# Micromouse_Arduino_Nano.net
KiCad netlist of a schematic drawn in EAGLE
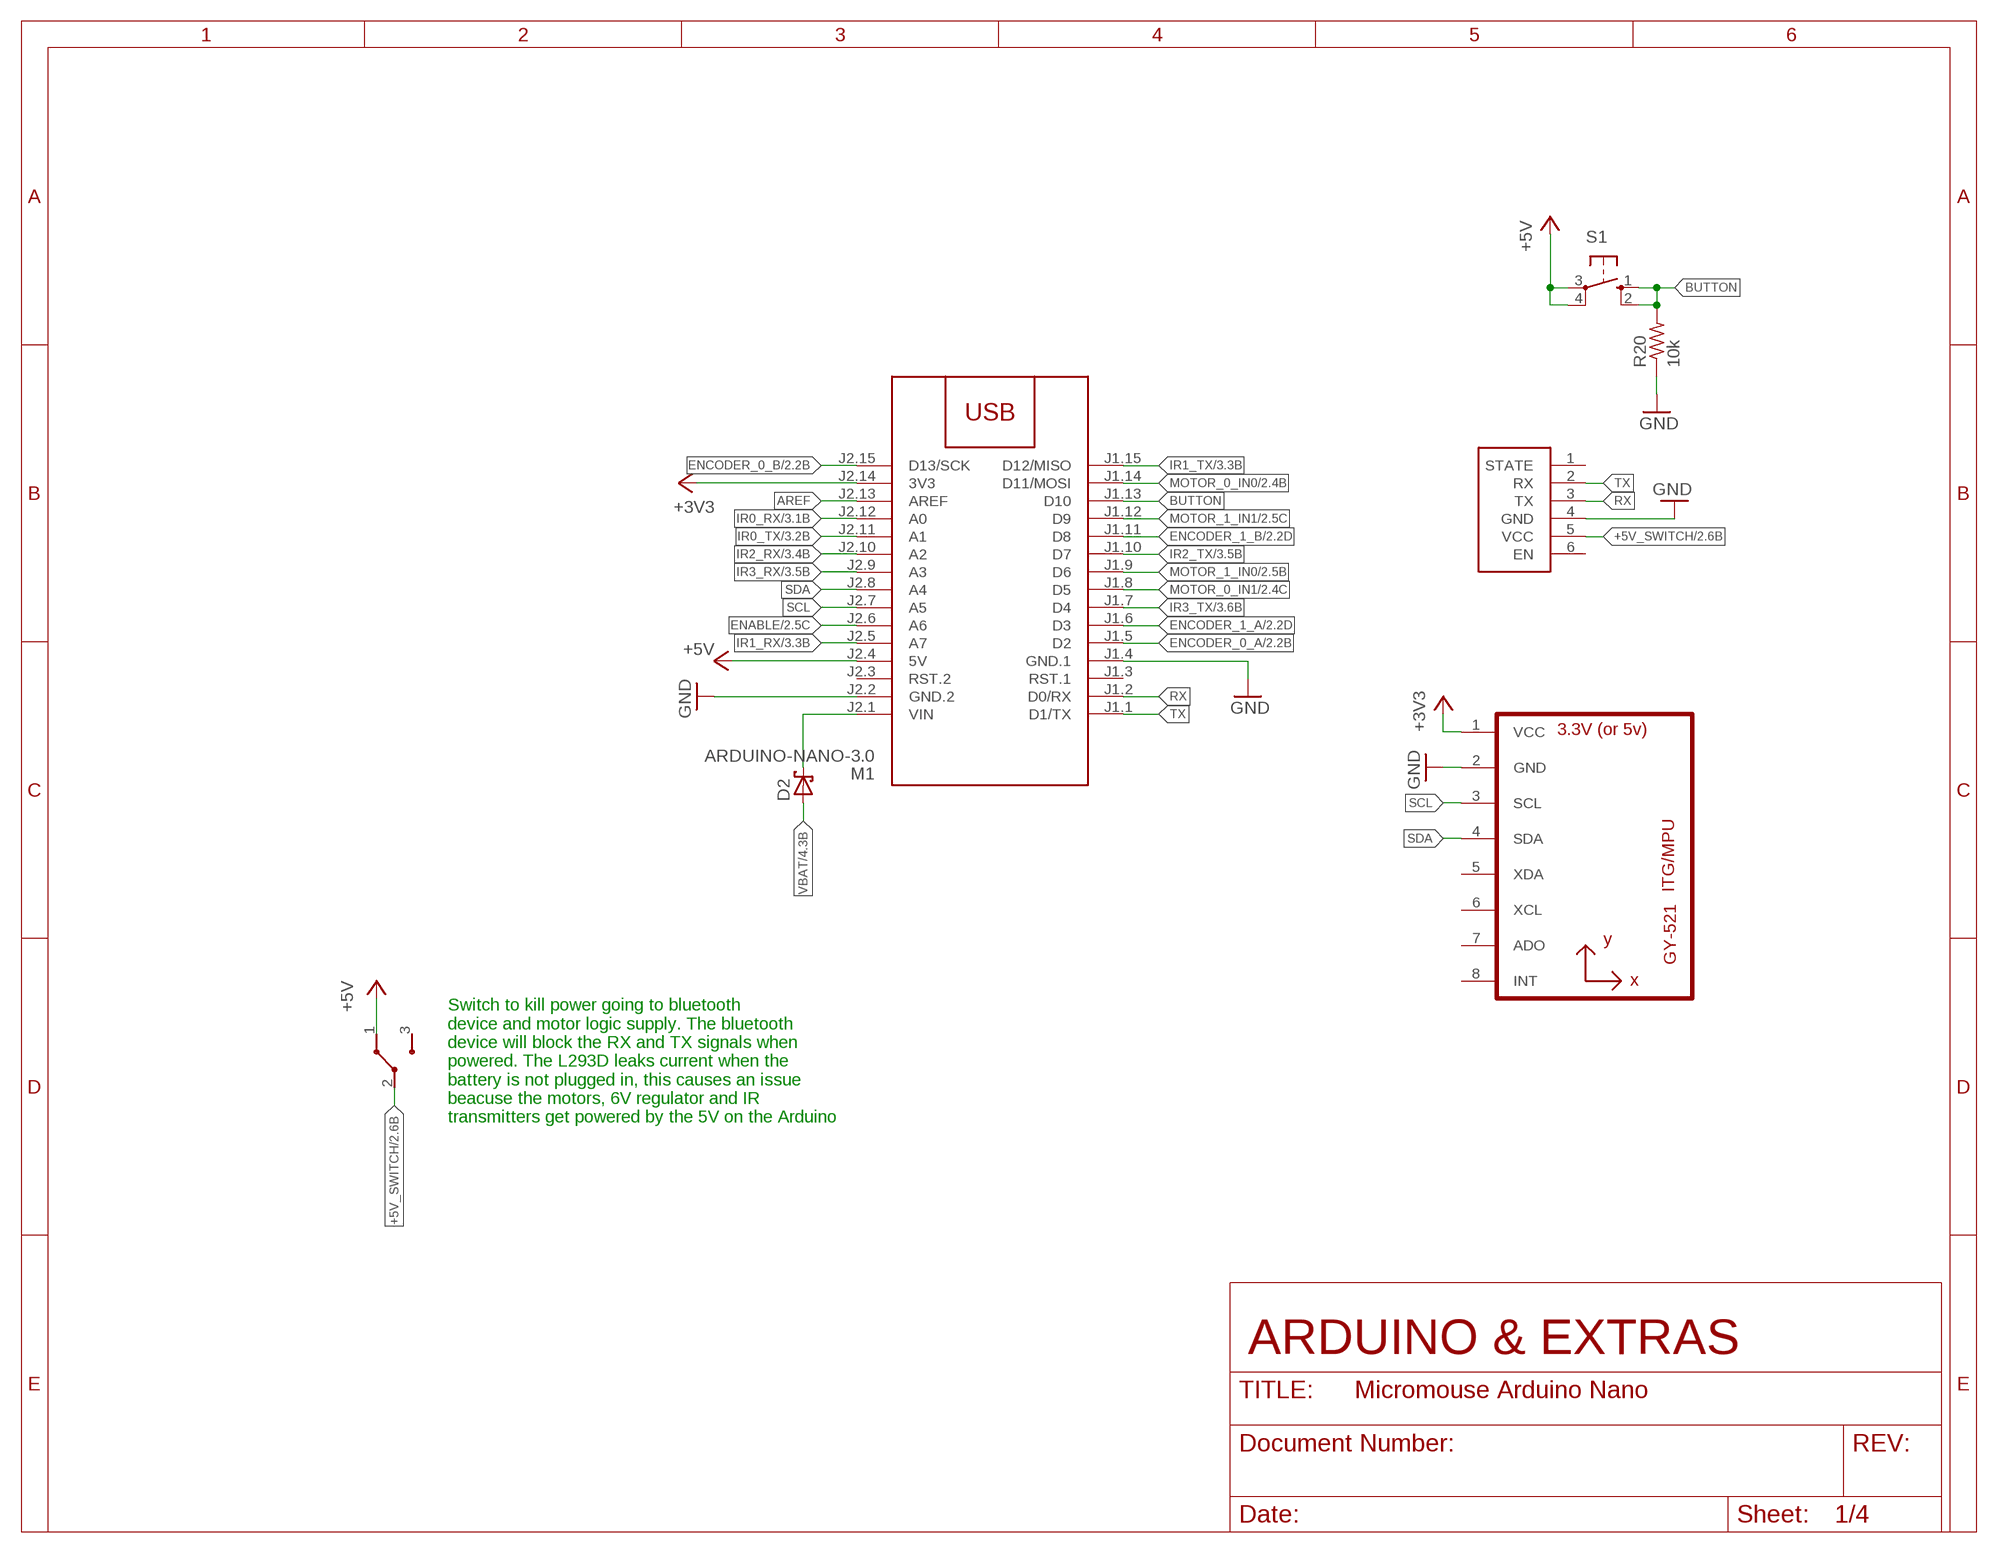
[diagram p0: schematic, sheet 1]
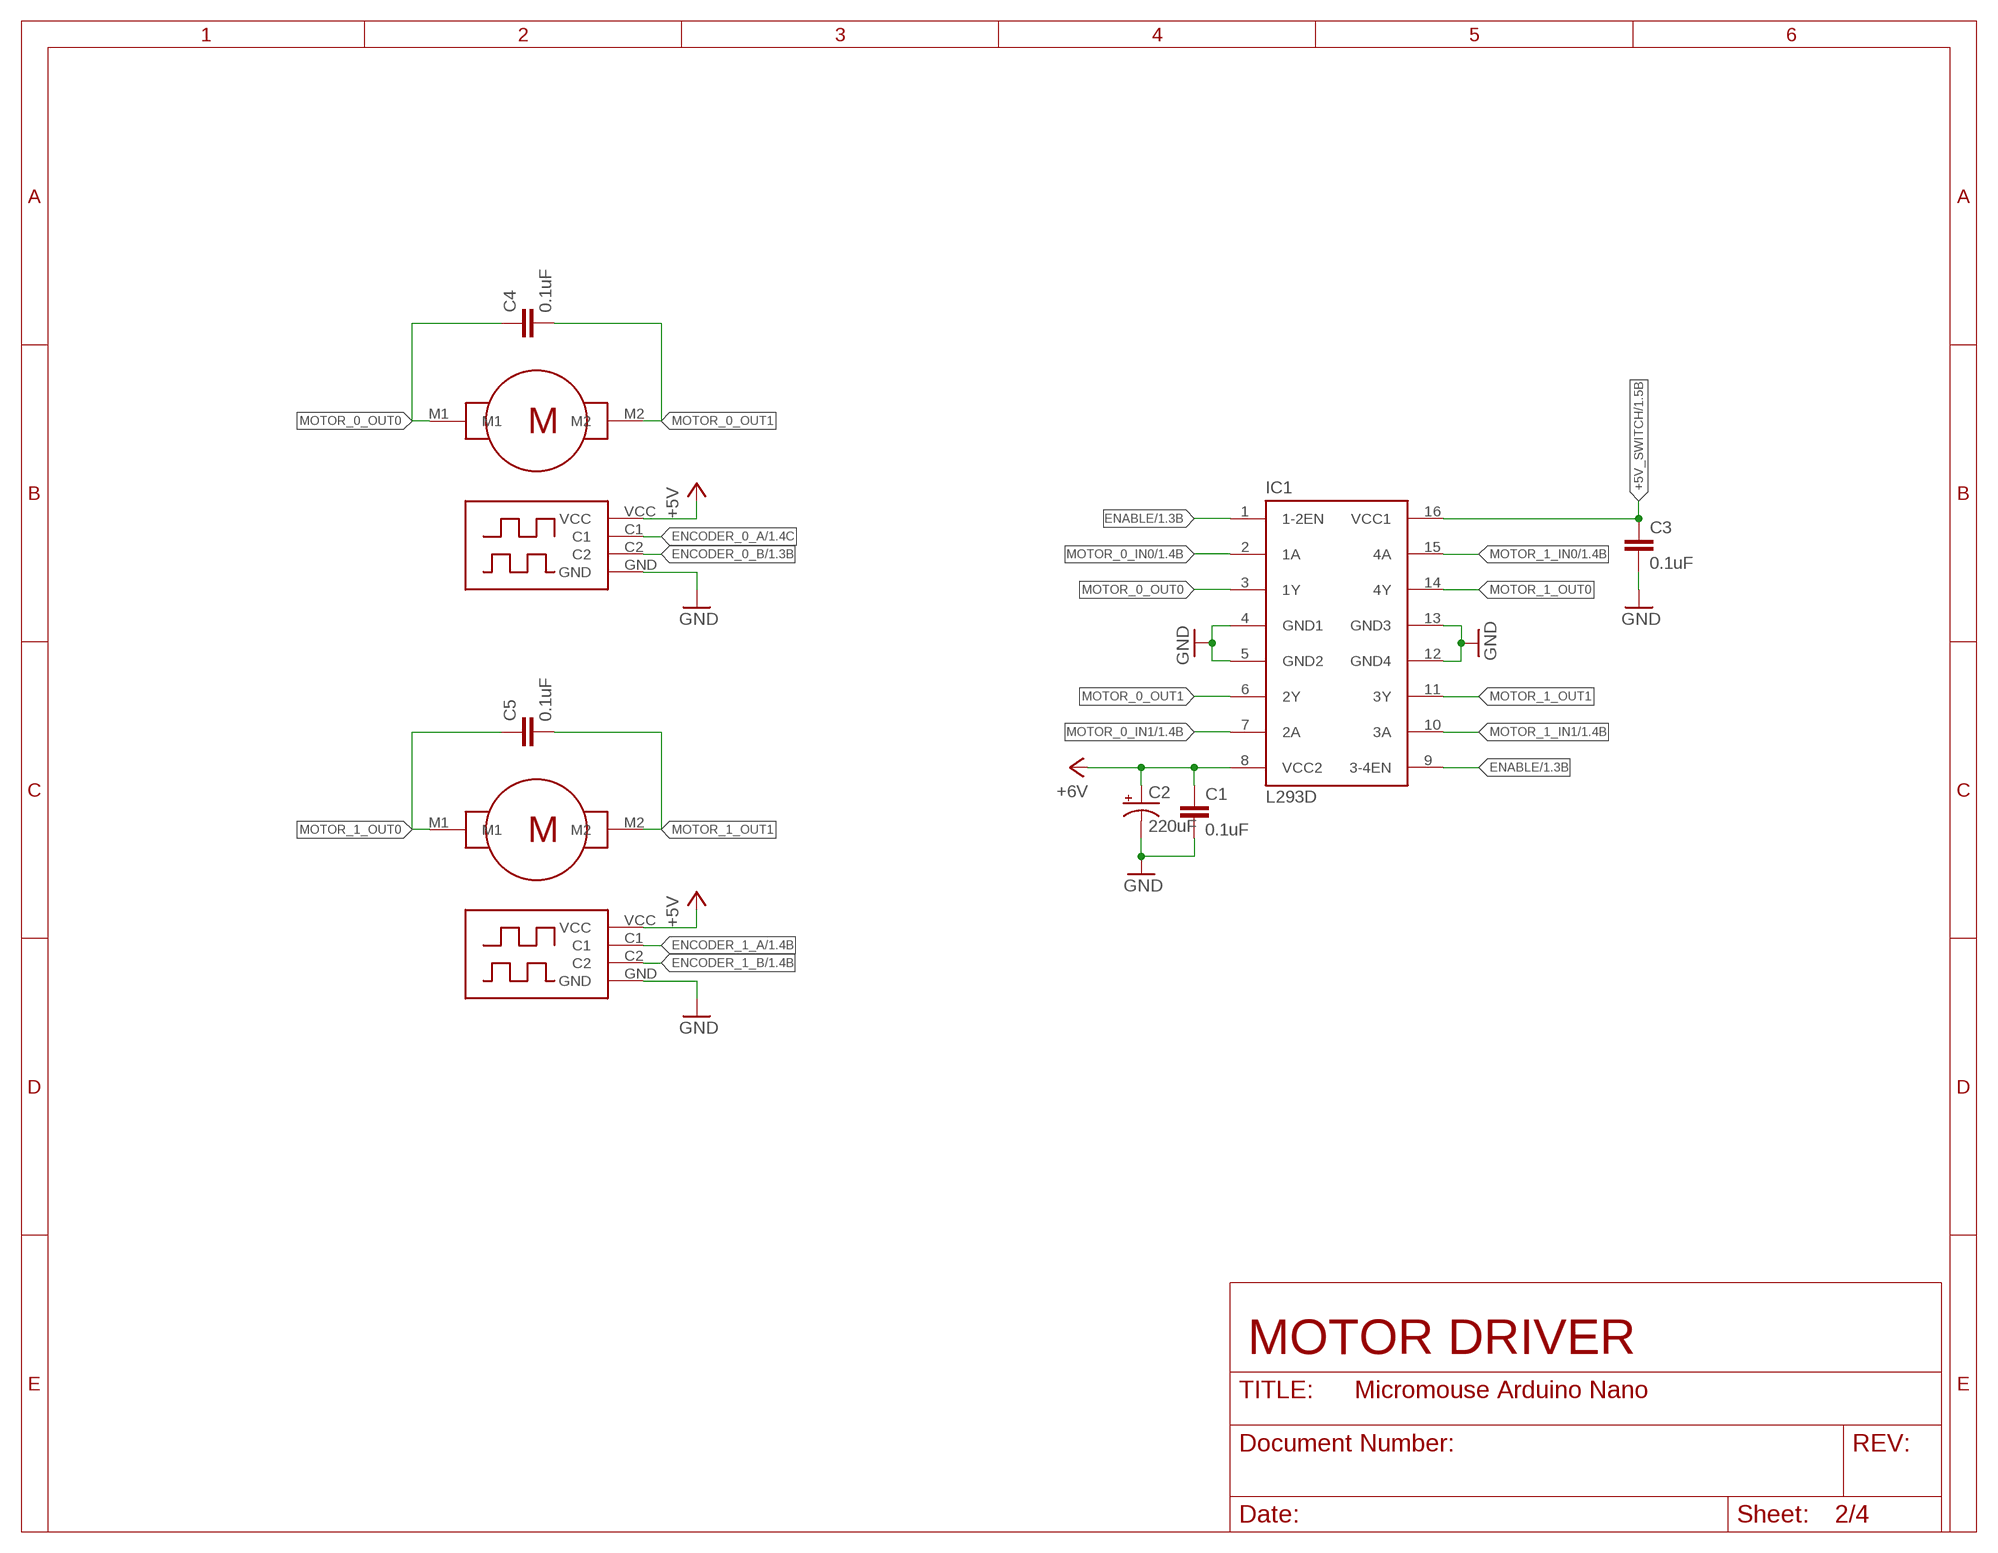
[diagram p1: schematic, sheet 2]
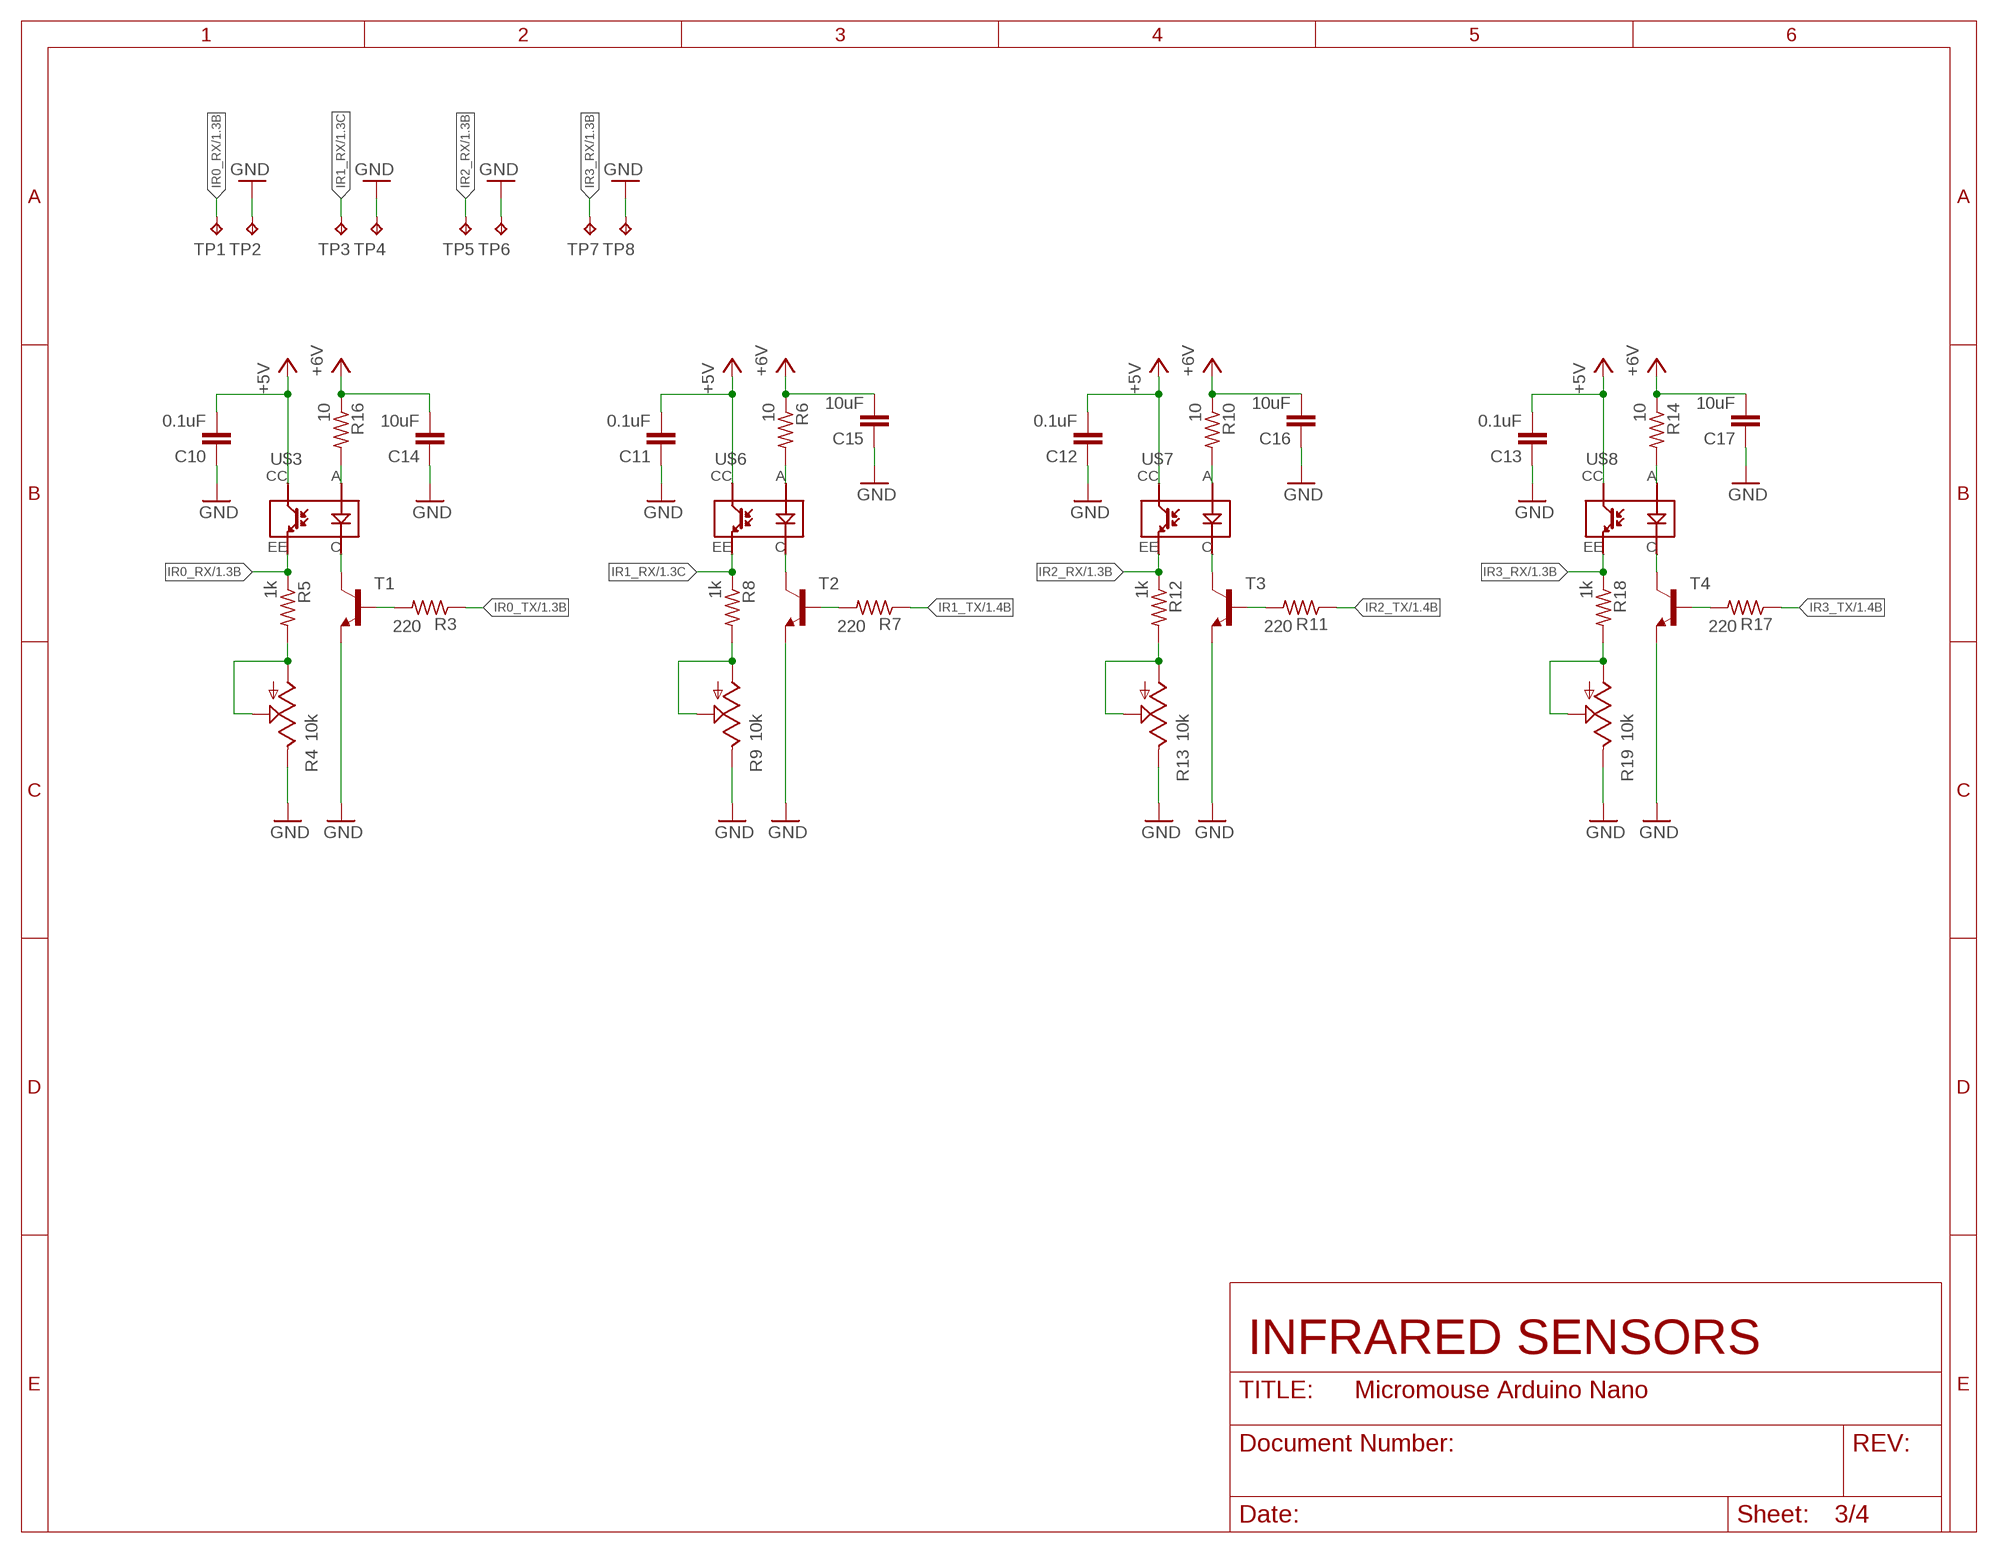
[diagram p2: schematic, sheet 3]
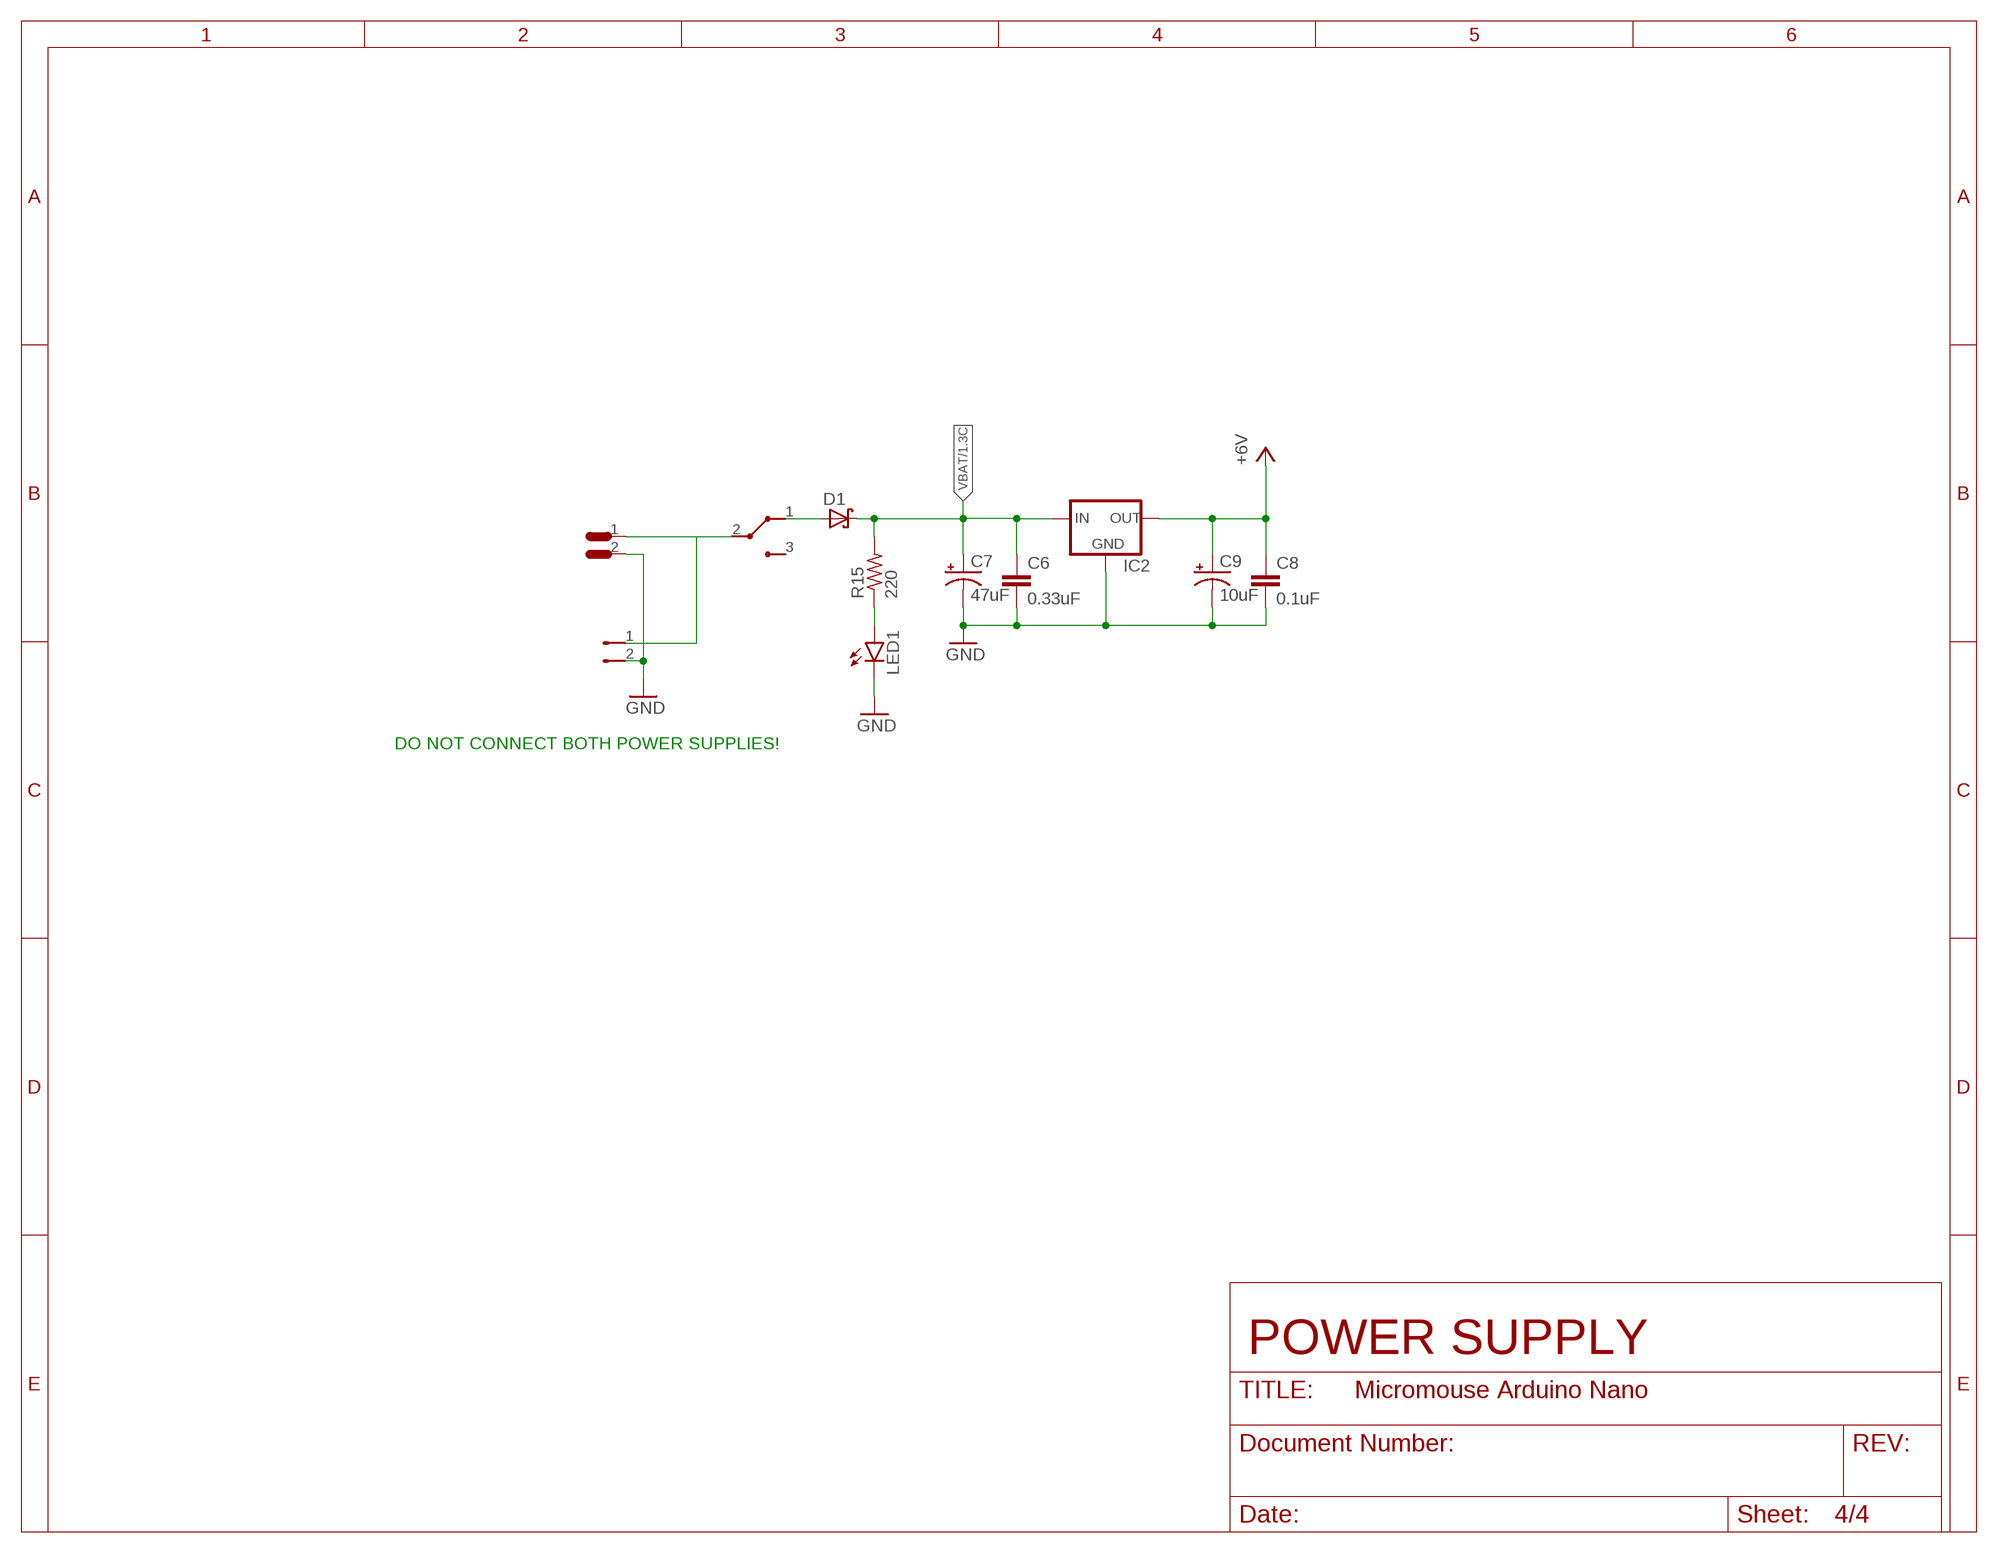
[diagram p3: schematic, sheet 4]

(export (version "E")
  (design (tool "Eeschema 10.0.6"))
  (components
    (comp (ref "C6")
      (value "0.33uF")
      (footprint "eagle-import:C050-025X075")
      (libsource (lib "eagle-import") (part "C-EU050-025X075"))
    )
    (comp (ref "C7")
      (value "47uF")
      (footprint "eagle-import:E2-4")
      (libsource (lib "eagle-import") (part "CPOL-USE2-4"))
    )
    (comp (ref "C8")
      (value "0.1uF")
      (footprint "eagle-import:C050-025X075")
      (libsource (lib "eagle-import") (part "C-EU050-025X075"))
    )
    (comp (ref "C9")
      (value "10uF")
      (footprint "eagle-import:E2,5-5")
      (libsource (lib "eagle-import") (part "CPOL-USE2.5-5"))
    )
    (comp (ref "D1")
      (value "SCHOTTKY-DIODEDO41-7")
      (footprint "eagle-import:DO41-7")
      (libsource (lib "eagle-import") (part "SCHOTTKY-DIODEDO41-7"))
    )
    (comp (ref "IC2")
      (value "78XXS")
      (footprint "eagle-import:78XXS")
      (libsource (lib "eagle-import") (part "78XXS"))
    )
    (comp (ref "LED1")
      (value "LED5MM")
      (footprint "eagle-import:LED5MM")
      (libsource (lib "eagle-import") (part "LED5MM"))
    )
    (comp (ref "R15")
      (value "220")
      (footprint "eagle-import:0207_2V")
      (libsource (lib "eagle-import") (part "R-US_0207/2V"))
    )
    (comp (ref "U$4")
      (value "K3-1260D")
      (footprint "eagle-import:K3-1260D")
      (libsource (lib "eagle-import") (part "K3-1260D"))
    )
    (comp (ref "U$5")
      (value "XT30-M")
      (footprint "eagle-import:XT30-M")
      (libsource (lib "eagle-import") (part "XT30-M"))
    )
    (comp (ref "U$12")
      (value "JST_POWER")
      (footprint "eagle-import:JST_POWER")
      (libsource (lib "eagle-import") (part "JST_POWER"))
    )
    (comp (ref "C1")
      (value "0.1uF")
      (footprint "eagle-import:C050-025X075")
      (libsource (lib "eagle-import") (part "C-EU050-025X075"))
    )
    (comp (ref "C2")
      (value "220uF")
      (footprint "eagle-import:E2,5-6")
      (libsource (lib "eagle-import") (part "CPOL-USE2.5-6"))
    )
    (comp (ref "C3")
      (value "0.1uF")
      (footprint "eagle-import:C050-025X075")
      (libsource (lib "eagle-import") (part "C-EU050-025X075"))
    )
    (comp (ref "C4")
      (value "0.1uF")
      (footprint "eagle-import:C050-025X075")
      (libsource (lib "eagle-import") (part "C-EU050-025X075"))
    )
    (comp (ref "C5")
      (value "0.1uF")
      (footprint "eagle-import:C050-025X075")
      (libsource (lib "eagle-import") (part "C-EU050-025X075"))
    )
    (comp (ref "IC1")
      (value "L293D")
      (footprint "eagle-import:DIL16")
      (libsource (lib "eagle-import") (part "L293D"))
    )
    (comp (ref "U$1")
      (value "DC_MOTOR")
      (footprint "eagle-import:DC_MOTOR")
      (libsource (lib "eagle-import") (part "DC_MOTOR"))
    )
    (comp (ref "U$2")
      (value "DC_MOTOR")
      (footprint "eagle-import:DC_MOTOR")
      (libsource (lib "eagle-import") (part "DC_MOTOR"))
    )
    (comp (ref "D2")
      (value "SCHOTTKY-DIODEDO41-7")
      (footprint "eagle-import:DO41-7")
      (libsource (lib "eagle-import") (part "SCHOTTKY-DIODEDO41-7"))
    )
    (comp (ref "M1")
      (value "ARDUINO-NANO-3.0")
      (footprint "eagle-import:ARDUINO-NANO-3.0")
      (libsource (lib "eagle-import") (part "ARDUINO-NANO-3.0"))
    )
    (comp (ref "R20")
      (value "10k")
      (footprint "eagle-import:0207_2V")
      (libsource (lib "eagle-import") (part "R-US_0207/2V"))
    )
    (comp (ref "S1")
      (value "10-XX")
      (footprint "eagle-import:B3F-10XX")
      (fields (field (name "MPN") "B3F-1000"))
      (libsource (lib "eagle-import") (part "10-XX"))
    )
    (comp (ref "U$9")
      (value "HC-05")
      (footprint "eagle-import:HC-05")
      (libsource (lib "eagle-import") (part "HC-05"))
    )
    (comp (ref "U$10")
      (value "K3-1260D")
      (footprint "eagle-import:K3-1260D")
      (libsource (lib "eagle-import") (part "K3-1260D"))
    )
    (comp (ref "U1")
      (value "GY-521MPU6050")
      (footprint "eagle-import:GY-521")
      (libsource (lib "eagle-import") (part "GY-521MPU6050"))
    )
    (comp (ref "C10")
      (value "0.1uF")
      (footprint "eagle-import:C050-025X075")
      (libsource (lib "eagle-import") (part "C-EU050-025X075"))
    )
    (comp (ref "C11")
      (value "0.1uF")
      (footprint "eagle-import:C050-025X075")
      (libsource (lib "eagle-import") (part "C-EU050-025X075"))
    )
    (comp (ref "C12")
      (value "0.1uF")
      (footprint "eagle-import:C050-025X075")
      (libsource (lib "eagle-import") (part "C-EU050-025X075"))
    )
    (comp (ref "C13")
      (value "0.1uF")
      (footprint "eagle-import:C050-025X075")
      (libsource (lib "eagle-import") (part "C-EU050-025X075"))
    )
    (comp (ref "C14")
      (value "10uF")
      (footprint "eagle-import:C050-025X075")
      (libsource (lib "eagle-import") (part "C-EU050-025X075"))
    )
    (comp (ref "C15")
      (value "10uF")
      (footprint "eagle-import:C050-025X075")
      (libsource (lib "eagle-import") (part "C-EU050-025X075"))
    )
    (comp (ref "C16")
      (value "10uF")
      (footprint "eagle-import:C050-025X075")
      (libsource (lib "eagle-import") (part "C-EU050-025X075"))
    )
    (comp (ref "C17")
      (value "10uF")
      (footprint "eagle-import:C050-025X075")
      (libsource (lib "eagle-import") (part "C-EU050-025X075"))
    )
    (comp (ref "R3")
      (value "220")
      (footprint "eagle-import:0207_2V")
      (libsource (lib "eagle-import") (part "R-US_0207/2V"))
    )
    (comp (ref "R4")
      (value "10k")
      (footprint "eagle-import:CT6")
      (libsource (lib "eagle-import") (part "TRIM_US-CT6"))
    )
    (comp (ref "R5")
      (value "1k")
      (footprint "eagle-import:0207_2V")
      (libsource (lib "eagle-import") (part "R-US_0207/2V"))
    )
    (comp (ref "R6")
      (value "10")
      (footprint "eagle-import:0207_2V")
      (libsource (lib "eagle-import") (part "R-US_0207/2V"))
    )
    (comp (ref "R7")
      (value "220")
      (footprint "eagle-import:0207_2V")
      (libsource (lib "eagle-import") (part "R-US_0207/2V"))
    )
    (comp (ref "R8")
      (value "1k")
      (footprint "eagle-import:0207_2V")
      (libsource (lib "eagle-import") (part "R-US_0207/2V"))
    )
    (comp (ref "R9")
      (value "10k")
      (footprint "eagle-import:CT6")
      (libsource (lib "eagle-import") (part "TRIM_US-CT6"))
    )
    (comp (ref "R10")
      (value "10")
      (footprint "eagle-import:0207_2V")
      (libsource (lib "eagle-import") (part "R-US_0207/2V"))
    )
    (comp (ref "R11")
      (value "220")
      (footprint "eagle-import:0207_2V")
      (libsource (lib "eagle-import") (part "R-US_0207/2V"))
    )
    (comp (ref "R12")
      (value "1k")
      (footprint "eagle-import:0207_2V")
      (libsource (lib "eagle-import") (part "R-US_0207/2V"))
    )
    (comp (ref "R13")
      (value "10k")
      (footprint "eagle-import:CT6")
      (libsource (lib "eagle-import") (part "TRIM_US-CT6"))
    )
    (comp (ref "R14")
      (value "10")
      (footprint "eagle-import:0207_2V")
      (libsource (lib "eagle-import") (part "R-US_0207/2V"))
    )
    (comp (ref "R16")
      (value "10")
      (footprint "eagle-import:0207_2V")
      (libsource (lib "eagle-import") (part "R-US_0207/2V"))
    )
    (comp (ref "R17")
      (value "220")
      (footprint "eagle-import:0207_2V")
      (libsource (lib "eagle-import") (part "R-US_0207/2V"))
    )
    (comp (ref "R18")
      (value "1k")
      (footprint "eagle-import:0207_2V")
      (libsource (lib "eagle-import") (part "R-US_0207/2V"))
    )
    (comp (ref "R19")
      (value "10k")
      (footprint "eagle-import:CT6")
      (libsource (lib "eagle-import") (part "TRIM_US-CT6"))
    )
    (comp (ref "T1")
      (value "2N4124-NPN-TO92-CBE")
      (footprint "eagle-import:TO92-CBE")
      (libsource (lib "eagle-import") (part "-NPN-TO92-CBE2N4124"))
    )
    (comp (ref "T2")
      (value "2N4124-NPN-TO92-CBE")
      (footprint "eagle-import:TO92-CBE")
      (libsource (lib "eagle-import") (part "-NPN-TO92-CBE2N4124"))
    )
    (comp (ref "T3")
      (value "2N4124-NPN-TO92-CBE")
      (footprint "eagle-import:TO92-CBE")
      (libsource (lib "eagle-import") (part "-NPN-TO92-CBE2N4124"))
    )
    (comp (ref "T4")
      (value "2N4124-NPN-TO92-CBE")
      (footprint "eagle-import:TO92-CBE")
      (libsource (lib "eagle-import") (part "-NPN-TO92-CBE2N4124"))
    )
    (comp (ref "TP1")
      (value "TPPAD1-13")
      (footprint "eagle-import:P1-13")
      (libsource (lib "eagle-import") (part "TPPAD1-13"))
    )
    (comp (ref "TP2")
      (value "TPPAD1-13")
      (footprint "eagle-import:P1-13")
      (libsource (lib "eagle-import") (part "TPPAD1-13"))
    )
    (comp (ref "TP3")
      (value "TPPAD1-13")
      (footprint "eagle-import:P1-13")
      (libsource (lib "eagle-import") (part "TPPAD1-13"))
    )
    (comp (ref "TP4")
      (value "TPPAD1-13")
      (footprint "eagle-import:P1-13")
      (libsource (lib "eagle-import") (part "TPPAD1-13"))
    )
    (comp (ref "TP5")
      (value "TPPAD1-13")
      (footprint "eagle-import:P1-13")
      (libsource (lib "eagle-import") (part "TPPAD1-13"))
    )
    (comp (ref "TP6")
      (value "TPPAD1-13")
      (footprint "eagle-import:P1-13")
      (libsource (lib "eagle-import") (part "TPPAD1-13"))
    )
    (comp (ref "TP7")
      (value "TPPAD1-13")
      (footprint "eagle-import:P1-13")
      (libsource (lib "eagle-import") (part "TPPAD1-13"))
    )
    (comp (ref "TP8")
      (value "TPPAD1-13")
      (footprint "eagle-import:P1-13")
      (libsource (lib "eagle-import") (part "TPPAD1-13"))
    )
    (comp (ref "U$3")
      (value "IR_DISTANCE_1X2")
      (footprint "eagle-import:IR_DISTANCE_1X2")
      (libsource (lib "eagle-import") (part "IR_DISTANCE_1X2"))
    )
    (comp (ref "U$6")
      (value "IR_DISTANCE_1X2")
      (footprint "eagle-import:IR_DISTANCE_1X2")
      (libsource (lib "eagle-import") (part "IR_DISTANCE_1X2"))
    )
    (comp (ref "U$7")
      (value "IR_DISTANCE_1X2")
      (footprint "eagle-import:IR_DISTANCE_1X2")
      (libsource (lib "eagle-import") (part "IR_DISTANCE_1X2"))
    )
    (comp (ref "U$8")
      (value "IR_DISTANCE_1X2")
      (footprint "eagle-import:IR_DISTANCE_1X2")
      (libsource (lib "eagle-import") (part "IR_DISTANCE_1X2"))
    )
  )
  (nets
    (net (code "1") (name "+3V3") (class "Default")
      (node (ref "M1") (pin "J2.14") (pinfunction "3V3_J2.14") (pintype "power_in"))
      (node (ref "U1") (pin "1") (pinfunction "VCC_1") (pintype "bidirectional"))
    )
    (net (code "2") (name "+5V") (class "Default")
      (node (ref "C10") (pin "2") (pinfunction "2_2") (pintype "passive"))
      (node (ref "C11") (pin "2") (pinfunction "2_2") (pintype "passive"))
      (node (ref "C12") (pin "2") (pinfunction "2_2") (pintype "passive"))
      (node (ref "C13") (pin "2") (pinfunction "2_2") (pintype "passive"))
      (node (ref "M1") (pin "J2.4") (pinfunction "5V_J2.4") (pintype "power_in"))
      (node (ref "S1") (pin "3") (pinfunction "P_3") (pintype "passive"))
      (node (ref "S1") (pin "4") (pinfunction "P1_4") (pintype "passive"))
      (node (ref "U$1") (pin "VCC") (pinfunction "VCC_VCC") (pintype "bidirectional"))
      (node (ref "U$10") (pin "1") (pinfunction "1_1") (pintype "bidirectional"))
      (node (ref "U$2") (pin "VCC") (pinfunction "VCC_VCC") (pintype "bidirectional"))
      (node (ref "U$3") (pin "CC") (pinfunction "CC_CC") (pintype "bidirectional"))
      (node (ref "U$6") (pin "CC") (pinfunction "CC_CC") (pintype "bidirectional"))
      (node (ref "U$7") (pin "CC") (pinfunction "CC_CC") (pintype "bidirectional"))
      (node (ref "U$8") (pin "CC") (pinfunction "CC_CC") (pintype "bidirectional"))
    )
    (net (code "3") (name "+5V_SWITCH") (class "Default")
      (node (ref "C3") (pin "1") (pinfunction "1_1") (pintype "passive"))
      (node (ref "IC1") (pin "16") (pinfunction "VCC1_16") (pintype "power_in"))
      (node (ref "U$10") (pin "2") (pinfunction "2_2") (pintype "bidirectional"))
      (node (ref "U$9") (pin "5") (pinfunction "VCC_5") (pintype "bidirectional"))
    )
    (net (code "4") (name "AREF") (class "Default")
      (node (ref "M1") (pin "J2.13") (pinfunction "AREF_J2.13") (pintype "bidirectional"))
    )
    (net (code "5") (name "BUTTON") (class "Default")
      (node (ref "M1") (pin "J1.13") (pinfunction "D10_J1.13") (pintype "bidirectional"))
      (node (ref "R20") (pin "2") (pinfunction "2_2") (pintype "passive"))
      (node (ref "S1") (pin "1") (pinfunction "S_1") (pintype "passive"))
      (node (ref "S1") (pin "2") (pinfunction "S1_2") (pintype "passive"))
    )
    (net (code "6") (name "ENABLE") (class "Default")
      (node (ref "IC1") (pin "1") (pinfunction "1-2EN_1") (pintype "input"))
      (node (ref "IC1") (pin "9") (pinfunction "3-4EN_9") (pintype "input"))
      (node (ref "M1") (pin "J2.6") (pinfunction "A6_J2.6") (pintype "bidirectional"))
    )
    (net (code "7") (name "ENCODER_0_A") (class "Default")
      (node (ref "M1") (pin "J1.5") (pinfunction "D2_J1.5") (pintype "bidirectional"))
      (node (ref "U$1") (pin "C1") (pinfunction "C1_C1") (pintype "bidirectional"))
    )
    (net (code "8") (name "ENCODER_0_B") (class "Default")
      (node (ref "M1") (pin "J2.15") (pinfunction "D13/SCK_J2.15") (pintype "bidirectional"))
      (node (ref "U$1") (pin "C2") (pinfunction "C2_C2") (pintype "bidirectional"))
    )
    (net (code "9") (name "ENCODER_1_A") (class "Default")
      (node (ref "M1") (pin "J1.6") (pinfunction "D3_J1.6") (pintype "bidirectional"))
      (node (ref "U$2") (pin "C1") (pinfunction "C1_C1") (pintype "bidirectional"))
    )
    (net (code "10") (name "ENCODER_1_B") (class "Default")
      (node (ref "M1") (pin "J1.11") (pinfunction "D8_J1.11") (pintype "bidirectional"))
      (node (ref "U$2") (pin "C2") (pinfunction "C2_C2") (pintype "bidirectional"))
    )
    (net (code "11") (name "GND") (class "Default")
      (node (ref "C1") (pin "2") (pinfunction "2_2") (pintype "passive"))
      (node (ref "C10") (pin "1") (pinfunction "1_1") (pintype "passive"))
      (node (ref "C11") (pin "1") (pinfunction "1_1") (pintype "passive"))
      (node (ref "C12") (pin "1") (pinfunction "1_1") (pintype "passive"))
      (node (ref "C13") (pin "1") (pinfunction "1_1") (pintype "passive"))
      (node (ref "C14") (pin "1") (pinfunction "1_1") (pintype "passive"))
      (node (ref "C15") (pin "1") (pinfunction "1_1") (pintype "passive"))
      (node (ref "C16") (pin "1") (pinfunction "1_1") (pintype "passive"))
      (node (ref "C17") (pin "1") (pinfunction "1_1") (pintype "passive"))
      (node (ref "C2") (pin "-") (pinfunction "-_-") (pintype "passive"))
      (node (ref "C3") (pin "2") (pinfunction "2_2") (pintype "passive"))
      (node (ref "C6") (pin "2") (pinfunction "2_2") (pintype "passive"))
      (node (ref "C7") (pin "-") (pinfunction "-_-") (pintype "passive"))
      (node (ref "C8") (pin "2") (pinfunction "2_2") (pintype "passive"))
      (node (ref "C9") (pin "-") (pinfunction "-_-") (pintype "passive"))
      (node (ref "IC1") (pin "12") (pinfunction "GND4_12") (pintype "power_in"))
      (node (ref "IC1") (pin "13") (pinfunction "GND3_13") (pintype "power_in"))
      (node (ref "IC1") (pin "4") (pinfunction "GND1_4") (pintype "power_in"))
      (node (ref "IC1") (pin "5") (pinfunction "GND2_5") (pintype "power_in"))
      (node (ref "IC2") (pin "GND") (pinfunction "GND_GND") (pintype "input"))
      (node (ref "LED1") (pin "K") (pinfunction "C_K") (pintype "passive"))
      (node (ref "M1") (pin "J1.4") (pinfunction "GND.1_J1.4") (pintype "power_in"))
      (node (ref "M1") (pin "J2.2") (pinfunction "GND.2_J2.2") (pintype "power_in"))
      (node (ref "R13") (pin "E") (pinfunction "E_E") (pintype "passive"))
      (node (ref "R19") (pin "E") (pinfunction "E_E") (pintype "passive"))
      (node (ref "R20") (pin "1") (pinfunction "1_1") (pintype "passive"))
      (node (ref "R4") (pin "E") (pinfunction "E_E") (pintype "passive"))
      (node (ref "R9") (pin "E") (pinfunction "E_E") (pintype "passive"))
      (node (ref "T1") (pin "E") (pinfunction "E_E") (pintype "passive"))
      (node (ref "T2") (pin "E") (pinfunction "E_E") (pintype "passive"))
      (node (ref "T3") (pin "E") (pinfunction "E_E") (pintype "passive"))
      (node (ref "T4") (pin "E") (pinfunction "E_E") (pintype "passive"))
      (node (ref "TP2") (pin "TP") (pinfunction "TP_TP") (pintype "input"))
      (node (ref "TP4") (pin "TP") (pinfunction "TP_TP") (pintype "input"))
      (node (ref "TP6") (pin "TP") (pinfunction "TP_TP") (pintype "input"))
      (node (ref "TP8") (pin "TP") (pinfunction "TP_TP") (pintype "input"))
      (node (ref "U$1") (pin "GND") (pinfunction "GND_GND") (pintype "bidirectional"))
      (node (ref "U$12") (pin "2") (pinfunction "2_2") (pintype "bidirectional"))
      (node (ref "U$2") (pin "GND") (pinfunction "GND_GND") (pintype "bidirectional"))
      (node (ref "U$5") (pin "2") (pinfunction "P$2_2") (pintype "bidirectional"))
      (node (ref "U$9") (pin "4") (pinfunction "GND_4") (pintype "bidirectional"))
      (node (ref "U1") (pin "2") (pinfunction "GND_2") (pintype "bidirectional"))
    )
    (net (code "12") (name "IR0_RX") (class "Default")
      (node (ref "M1") (pin "J2.12") (pinfunction "A0_J2.12") (pintype "bidirectional"))
      (node (ref "R5") (pin "1") (pinfunction "1_1") (pintype "passive"))
      (node (ref "TP1") (pin "TP") (pinfunction "TP_TP") (pintype "input"))
      (node (ref "U$3") (pin "EE") (pinfunction "EE_EE") (pintype "bidirectional"))
    )
    (net (code "13") (name "IR0_TX") (class "Default")
      (node (ref "M1") (pin "J2.11") (pinfunction "A1_J2.11") (pintype "bidirectional"))
      (node (ref "R3") (pin "1") (pinfunction "1_1") (pintype "passive"))
    )
    (net (code "14") (name "IR1_RX") (class "Default")
      (node (ref "M1") (pin "J2.5") (pinfunction "A7_J2.5") (pintype "bidirectional"))
      (node (ref "R8") (pin "1") (pinfunction "1_1") (pintype "passive"))
      (node (ref "TP3") (pin "TP") (pinfunction "TP_TP") (pintype "input"))
      (node (ref "U$6") (pin "EE") (pinfunction "EE_EE") (pintype "bidirectional"))
    )
    (net (code "15") (name "IR1_TX") (class "Default")
      (node (ref "M1") (pin "J1.15") (pinfunction "D12/MISO_J1.15") (pintype "bidirectional"))
      (node (ref "R7") (pin "1") (pinfunction "1_1") (pintype "passive"))
    )
    (net (code "16") (name "IR2_RX") (class "Default")
      (node (ref "M1") (pin "J2.10") (pinfunction "A2_J2.10") (pintype "bidirectional"))
      (node (ref "R12") (pin "1") (pinfunction "1_1") (pintype "passive"))
      (node (ref "TP5") (pin "TP") (pinfunction "TP_TP") (pintype "input"))
      (node (ref "U$7") (pin "EE") (pinfunction "EE_EE") (pintype "bidirectional"))
    )
    (net (code "17") (name "IR2_TX") (class "Default")
      (node (ref "M1") (pin "J1.10") (pinfunction "D7_J1.10") (pintype "bidirectional"))
      (node (ref "R11") (pin "1") (pinfunction "1_1") (pintype "passive"))
    )
    (net (code "18") (name "IR3_RX") (class "Default")
      (node (ref "M1") (pin "J2.9") (pinfunction "A3_J2.9") (pintype "bidirectional"))
      (node (ref "R18") (pin "1") (pinfunction "1_1") (pintype "passive"))
      (node (ref "TP7") (pin "TP") (pinfunction "TP_TP") (pintype "input"))
      (node (ref "U$8") (pin "EE") (pinfunction "EE_EE") (pintype "bidirectional"))
    )
    (net (code "19") (name "IR3_TX") (class "Default")
      (node (ref "M1") (pin "J1.7") (pinfunction "D4_J1.7") (pintype "bidirectional"))
      (node (ref "R17") (pin "1") (pinfunction "1_1") (pintype "passive"))
    )
    (net (code "20") (name "MOTOR_0_IN0") (class "Default")
      (node (ref "IC1") (pin "2") (pinfunction "1A_2") (pintype "input"))
      (node (ref "M1") (pin "J1.14") (pinfunction "D11/MOSI_J1.14") (pintype "bidirectional"))
    )
    (net (code "21") (name "MOTOR_0_IN1") (class "Default")
      (node (ref "IC1") (pin "7") (pinfunction "2A_7") (pintype "input"))
      (node (ref "M1") (pin "J1.8") (pinfunction "D5_J1.8") (pintype "bidirectional"))
    )
    (net (code "22") (name "MOTOR_0_OUT0") (class "Default")
      (node (ref "C4") (pin "1") (pinfunction "1_1") (pintype "passive"))
      (node (ref "IC1") (pin "3") (pinfunction "1Y_3") (pintype "output"))
      (node (ref "U$1") (pin "M1") (pinfunction "M1_M1") (pintype "bidirectional"))
    )
    (net (code "23") (name "MOTOR_0_OUT1") (class "Default")
      (node (ref "C4") (pin "2") (pinfunction "2_2") (pintype "passive"))
      (node (ref "IC1") (pin "6") (pinfunction "2Y_6") (pintype "output"))
      (node (ref "U$1") (pin "M2") (pinfunction "M2_M2") (pintype "bidirectional"))
    )
    (net (code "24") (name "MOTOR_1_IN0") (class "Default")
      (node (ref "IC1") (pin "15") (pinfunction "4A_15") (pintype "input"))
      (node (ref "M1") (pin "J1.9") (pinfunction "D6_J1.9") (pintype "bidirectional"))
    )
    (net (code "25") (name "MOTOR_1_IN1") (class "Default")
      (node (ref "IC1") (pin "10") (pinfunction "3A_10") (pintype "input"))
      (node (ref "M1") (pin "J1.12") (pinfunction "D9_J1.12") (pintype "bidirectional"))
    )
    (net (code "26") (name "MOTOR_1_OUT0") (class "Default")
      (node (ref "C5") (pin "1") (pinfunction "1_1") (pintype "passive"))
      (node (ref "IC1") (pin "14") (pinfunction "4Y_14") (pintype "output"))
      (node (ref "U$2") (pin "M1") (pinfunction "M1_M1") (pintype "bidirectional"))
    )
    (net (code "27") (name "MOTOR_1_OUT1") (class "Default")
      (node (ref "C5") (pin "2") (pinfunction "2_2") (pintype "passive"))
      (node (ref "IC1") (pin "11") (pinfunction "3Y_11") (pintype "output"))
      (node (ref "U$2") (pin "M2") (pinfunction "M2_M2") (pintype "bidirectional"))
    )
    (net (code "28") (name "Net-(D1-PadA)") (class "Default")
      (node (ref "D1") (pin "A") (pinfunction "A_A") (pintype "passive"))
      (node (ref "U$4") (pin "1") (pinfunction "1_1") (pintype "bidirectional"))
    )
    (net (code "29") (name "Net-(LED1-PadA)") (class "Default")
      (node (ref "LED1") (pin "A") (pinfunction "A_A") (pintype "passive"))
      (node (ref "R15") (pin "1") (pinfunction "1_1") (pintype "passive"))
    )
    (net (code "30") (name "Net-(M1-VIN)") (class "Default")
      (node (ref "D2") (pin "C") (pinfunction "C_C") (pintype "passive"))
      (node (ref "M1") (pin "J2.1") (pinfunction "VIN_J2.1") (pintype "power_in"))
    )
    (net (code "31") (name "Net-(R3-Pad2)") (class "Default")
      (node (ref "R3") (pin "2") (pinfunction "2_2") (pintype "passive"))
      (node (ref "T1") (pin "B") (pinfunction "B_B") (pintype "passive"))
    )
    (net (code "32") (name "Net-(R4-PadA)") (class "Default")
      (node (ref "R4") (pin "A") (pinfunction "A_A") (pintype "passive"))
      (node (ref "R4") (pin "S") (pinfunction "S_S") (pintype "passive"))
      (node (ref "R5") (pin "2") (pinfunction "2_2") (pintype "passive"))
    )
    (net (code "33") (name "Net-(R6-Pad2)") (class "Default")
      (node (ref "R6") (pin "2") (pinfunction "2_2") (pintype "passive"))
      (node (ref "U$6") (pin "A") (pinfunction "A_A") (pintype "bidirectional"))
    )
    (net (code "34") (name "Net-(R7-Pad2)") (class "Default")
      (node (ref "R7") (pin "2") (pinfunction "2_2") (pintype "passive"))
      (node (ref "T2") (pin "B") (pinfunction "B_B") (pintype "passive"))
    )
    (net (code "35") (name "Net-(R8-Pad2)") (class "Default")
      (node (ref "R8") (pin "2") (pinfunction "2_2") (pintype "passive"))
      (node (ref "R9") (pin "A") (pinfunction "A_A") (pintype "passive"))
      (node (ref "R9") (pin "S") (pinfunction "S_S") (pintype "passive"))
    )
    (net (code "36") (name "Net-(R10-Pad2)") (class "Default")
      (node (ref "R10") (pin "2") (pinfunction "2_2") (pintype "passive"))
      (node (ref "U$7") (pin "A") (pinfunction "A_A") (pintype "bidirectional"))
    )
    (net (code "37") (name "Net-(R11-Pad2)") (class "Default")
      (node (ref "R11") (pin "2") (pinfunction "2_2") (pintype "passive"))
      (node (ref "T3") (pin "B") (pinfunction "B_B") (pintype "passive"))
    )
    (net (code "38") (name "Net-(R12-Pad2)") (class "Default")
      (node (ref "R12") (pin "2") (pinfunction "2_2") (pintype "passive"))
      (node (ref "R13") (pin "A") (pinfunction "A_A") (pintype "passive"))
      (node (ref "R13") (pin "S") (pinfunction "S_S") (pintype "passive"))
    )
    (net (code "39") (name "Net-(R14-Pad2)") (class "Default")
      (node (ref "R14") (pin "2") (pinfunction "2_2") (pintype "passive"))
      (node (ref "U$8") (pin "A") (pinfunction "A_A") (pintype "bidirectional"))
    )
    (net (code "40") (name "Net-(R16-Pad2)") (class "Default")
      (node (ref "R16") (pin "2") (pinfunction "2_2") (pintype "passive"))
      (node (ref "U$3") (pin "A") (pinfunction "A_A") (pintype "bidirectional"))
    )
    (net (code "41") (name "Net-(R17-Pad2)") (class "Default")
      (node (ref "R17") (pin "2") (pinfunction "2_2") (pintype "passive"))
      (node (ref "T4") (pin "B") (pinfunction "B_B") (pintype "passive"))
    )
    (net (code "42") (name "Net-(R18-Pad2)") (class "Default")
      (node (ref "R18") (pin "2") (pinfunction "2_2") (pintype "passive"))
      (node (ref "R19") (pin "A") (pinfunction "A_A") (pintype "passive"))
      (node (ref "R19") (pin "S") (pinfunction "S_S") (pintype "passive"))
    )
    (net (code "43") (name "Net-(T1-PadC)") (class "Default")
      (node (ref "T1") (pin "C") (pinfunction "C_C") (pintype "passive"))
      (node (ref "U$3") (pin "C") (pinfunction "C_C") (pintype "bidirectional"))
    )
    (net (code "44") (name "Net-(T2-PadC)") (class "Default")
      (node (ref "T2") (pin "C") (pinfunction "C_C") (pintype "passive"))
      (node (ref "U$6") (pin "C") (pinfunction "C_C") (pintype "bidirectional"))
    )
    (net (code "45") (name "Net-(T3-PadC)") (class "Default")
      (node (ref "T3") (pin "C") (pinfunction "C_C") (pintype "passive"))
      (node (ref "U$7") (pin "C") (pinfunction "C_C") (pintype "bidirectional"))
    )
    (net (code "46") (name "Net-(T4-PadC)") (class "Default")
      (node (ref "T4") (pin "C") (pinfunction "C_C") (pintype "passive"))
      (node (ref "U$8") (pin "C") (pinfunction "C_C") (pintype "bidirectional"))
    )
    (net (code "47") (name "Net-(U$5-P$1)") (class "Default")
      (node (ref "U$12") (pin "1") (pinfunction "1_1") (pintype "bidirectional"))
      (node (ref "U$4") (pin "2") (pinfunction "2_2") (pintype "bidirectional"))
      (node (ref "U$5") (pin "1") (pinfunction "P$1_1") (pintype "bidirectional"))
    )
    (net (code "48") (name "RX") (class "Default")
      (node (ref "M1") (pin "J1.2") (pinfunction "D0/RX_J1.2") (pintype "bidirectional"))
      (node (ref "U$9") (pin "3") (pinfunction "TX_3") (pintype "bidirectional"))
    )
    (net (code "49") (name "SCL") (class "Default")
      (node (ref "M1") (pin "J2.7") (pinfunction "A5_J2.7") (pintype "bidirectional"))
      (node (ref "U1") (pin "3") (pinfunction "SCL_3") (pintype "bidirectional"))
    )
    (net (code "50") (name "SDA") (class "Default")
      (node (ref "M1") (pin "J2.8") (pinfunction "A4_J2.8") (pintype "bidirectional"))
      (node (ref "U1") (pin "4") (pinfunction "SDA_4") (pintype "bidirectional"))
    )
    (net (code "51") (name "TX") (class "Default")
      (node (ref "M1") (pin "J1.1") (pinfunction "D1/TX_J1.1") (pintype "bidirectional"))
      (node (ref "U$9") (pin "2") (pinfunction "RX_2") (pintype "bidirectional"))
    )
    (net (code "52") (name "VBAT") (class "Default")
      (node (ref "C6") (pin "1") (pinfunction "1_1") (pintype "passive"))
      (node (ref "C7") (pin "+") (pinfunction "+_+") (pintype "passive"))
      (node (ref "D1") (pin "C") (pinfunction "C_C") (pintype "passive"))
      (node (ref "D2") (pin "A") (pinfunction "A_A") (pintype "passive"))
      (node (ref "IC2") (pin "IN") (pinfunction "IN_IN") (pintype "input"))
      (node (ref "R15") (pin "2") (pinfunction "2_2") (pintype "passive"))
    )
    (net (code "53") (name "VCC") (class "Default")
      (node (ref "C1") (pin "1") (pinfunction "1_1") (pintype "passive"))
      (node (ref "C14") (pin "2") (pinfunction "2_2") (pintype "passive"))
      (node (ref "C15") (pin "2") (pinfunction "2_2") (pintype "passive"))
      (node (ref "C16") (pin "2") (pinfunction "2_2") (pintype "passive"))
      (node (ref "C17") (pin "2") (pinfunction "2_2") (pintype "passive"))
      (node (ref "C2") (pin "+") (pinfunction "+_+") (pintype "passive"))
      (node (ref "C8") (pin "1") (pinfunction "1_1") (pintype "passive"))
      (node (ref "C9") (pin "+") (pinfunction "+_+") (pintype "passive"))
      (node (ref "IC1") (pin "8") (pinfunction "VCC2_8") (pintype "power_in"))
      (node (ref "IC2") (pin "OUT") (pinfunction "OUT_OUT") (pintype "passive"))
      (node (ref "R10") (pin "1") (pinfunction "1_1") (pintype "passive"))
      (node (ref "R14") (pin "1") (pinfunction "1_1") (pintype "passive"))
      (node (ref "R16") (pin "1") (pinfunction "1_1") (pintype "passive"))
      (node (ref "R6") (pin "1") (pinfunction "1_1") (pintype "passive"))
    )
    (net (code "54") (name "unconnected-(M1-RST.1-PadJ1.3)") (class "Default")
      (node (ref "M1") (pin "J1.3") (pinfunction "RST.1_J1.3") (pintype "bidirectional"))
    )
    (net (code "55") (name "unconnected-(M1-RST.2-PadJ2.3)") (class "Default")
      (node (ref "M1") (pin "J2.3") (pinfunction "RST.2_J2.3") (pintype "bidirectional"))
    )
    (net (code "56") (name "unconnected-(U$4-Pad3)") (class "Default")
      (node (ref "U$4") (pin "3") (pinfunction "3_3") (pintype "bidirectional"))
    )
    (net (code "57") (name "unconnected-(U$9-EN-Pad6)") (class "Default")
      (node (ref "U$9") (pin "6") (pinfunction "EN_6") (pintype "bidirectional"))
    )
    (net (code "58") (name "unconnected-(U$9-STATE-Pad1)") (class "Default")
      (node (ref "U$9") (pin "1") (pinfunction "STATE_1") (pintype "bidirectional"))
    )
    (net (code "59") (name "unconnected-(U$10-Pad3)") (class "Default")
      (node (ref "U$10") (pin "3") (pinfunction "3_3") (pintype "bidirectional"))
    )
    (net (code "60") (name "unconnected-(U1-ADO-Pad7)") (class "Default")
      (node (ref "U1") (pin "7") (pinfunction "ADO_7") (pintype "bidirectional"))
    )
    (net (code "61") (name "unconnected-(U1-INT-Pad8)") (class "Default")
      (node (ref "U1") (pin "8") (pinfunction "INT_8") (pintype "bidirectional"))
    )
    (net (code "62") (name "unconnected-(U1-XCL-Pad6)") (class "Default")
      (node (ref "U1") (pin "6") (pinfunction "XCL_6") (pintype "bidirectional"))
    )
    (net (code "63") (name "unconnected-(U1-XDA-Pad5)") (class "Default")
      (node (ref "U1") (pin "5") (pinfunction "XDA_5") (pintype "bidirectional"))
    )
  )
)
